# CAA-NMC_variants.net
KiCad netlist of a schematic drawn in EAGLE
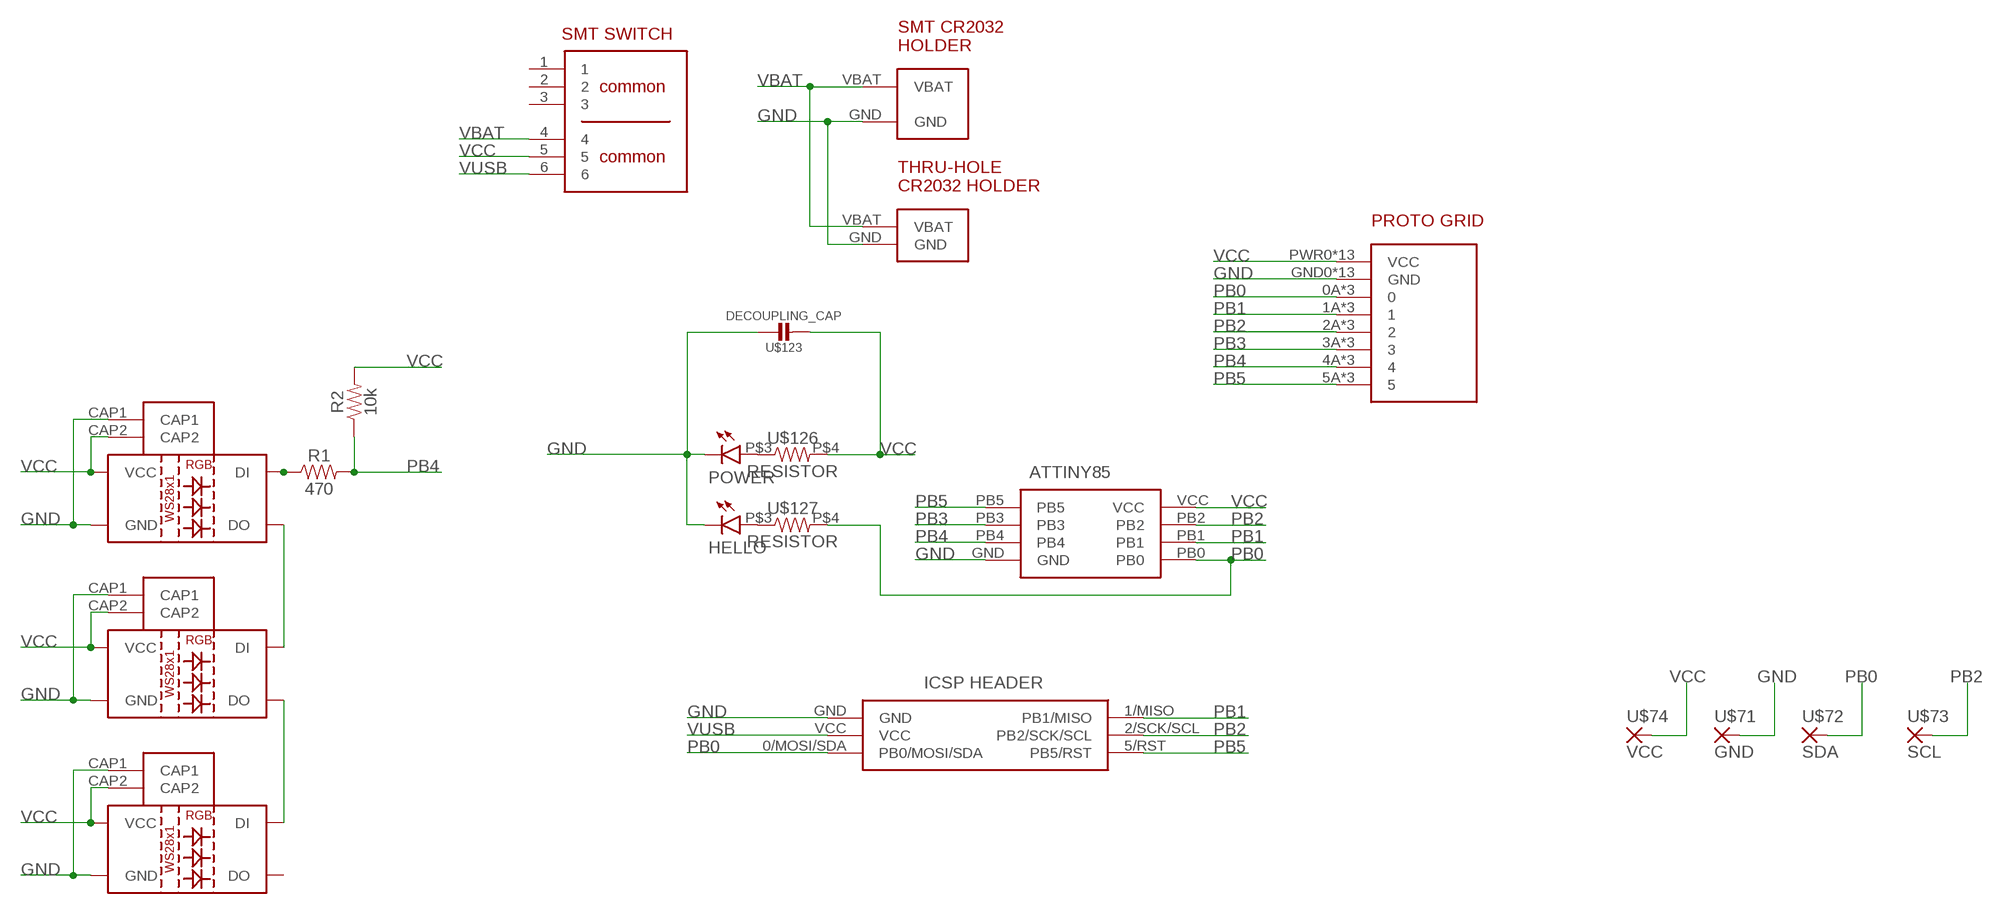
[diagram p0: schematic, sheet 1]

(export (version "E")
  (design (tool "Eeschema 10.0.6"))
  (components
    (comp (ref "D1")
      (value "WS2812B")
      (footprint "eagle-import:WS2812B")
      (libsource (lib "eagle-import") (part "WS2812B"))
    )
    (comp (ref "D2")
      (value "WS2812B")
      (footprint "eagle-import:WS2812B")
      (libsource (lib "eagle-import") (part "WS2812B"))
    )
    (comp (ref "D3")
      (value "WS2812B")
      (footprint "eagle-import:WS2812B")
      (libsource (lib "eagle-import") (part "WS2812B"))
    )
    (comp (ref "HELLO")
      (value "LED3MM")
      (footprint "eagle-import:LED3MM")
      (libsource (lib "eagle-import") (part "LED3MM"))
    )
    (comp (ref "IC1")
      (value "ATTINY85-20SU")
      (footprint "eagle-import:SOT127P798X216-8N")
      (fields (field (name "RS_PART_NUMBER") "1331674"))
      (libsource (lib "eagle-import") (part "ATTINY85-20SU"))
    )
    (comp (ref "J1")
      (value "M20-9980346")
      (footprint "eagle-import:HDRV6W64P254_2X3_762X508X868P")
      (fields (field (name "RS_PART_NUMBER") "7457046P"))
      (libsource (lib "eagle-import") (part "M20-9980346"))
    )
    (comp (ref "POWER")
      (value "LED3MM")
      (footprint "eagle-import:LED3MM")
      (libsource (lib "eagle-import") (part "LED3MM"))
    )
    (comp (ref "R1")
      (value "470")
      (footprint "eagle-import:0603")
      (libsource (lib "eagle-import") (part "470OHM-0603-1/10W-1%"))
    )
    (comp (ref "R2")
      (value "10k")
      (footprint "eagle-import:0603")
      (libsource (lib "eagle-import") (part "10KOHM-0603-1/10W-1%"))
    )
    (comp (ref "U$1")
      (value "PROTO")
      (footprint "eagle-import:PROTO")
      (libsource (lib "eagle-import") (part "PROTO"))
    )
    (comp (ref "U$2")
      (value "SMT-BATTERY-HOLDER")
      (footprint "eagle-import:SMT-CR-HOLDER")
      (libsource (lib "eagle-import") (part "SMT-BATTERY-HOLDER"))
    )
    (comp (ref "U$3")
      (value "THRU-CR-HOLDER")
      (footprint "eagle-import:THRU-CR-HOLDER")
      (libsource (lib "eagle-import") (part "THRU-CR-HOLDER"))
    )
    (comp (ref "U$71")
      (value "GND")
      (footprint "eagle-import:1X01")
      (libsource (lib "eagle-import") (part "ONE_PAD"))
    )
    (comp (ref "U$72")
      (value "SDA")
      (footprint "eagle-import:1X01")
      (libsource (lib "eagle-import") (part "ONE_PAD"))
    )
    (comp (ref "U$73")
      (value "SCL")
      (footprint "eagle-import:1X01")
      (libsource (lib "eagle-import") (part "ONE_PAD"))
    )
    (comp (ref "U$74")
      (value "VCC")
      (footprint "eagle-import:1X01")
      (libsource (lib "eagle-import") (part "ONE_PAD"))
    )
    (comp (ref "U$123")
      (value "DECOUPLING_CAP")
      (footprint "eagle-import:DECOUPLING_CAP")
      (libsource (lib "eagle-import") (part "DECOUPLING_CAP"))
    )
    (comp (ref "U$126")
      (value "RESISTOR")
      (footprint "eagle-import:AXIAL-0.3")
      (libsource (lib "eagle-import") (part "RESISTOR"))
    )
    (comp (ref "U$127")
      (value "RESISTOR")
      (footprint "eagle-import:AXIAL-0.3")
      (libsource (lib "eagle-import") (part "RESISTOR"))
    )
    (comp (ref "U$145")
      (value "SMT-SWITCH")
      (footprint "eagle-import:SMT-SWITCH")
      (libsource (lib "eagle-import") (part "SMT-SWITCH"))
    )
  )
  (nets
    (net (code "1") (name "/GND") (class "Default")
      (node (ref "D1") (pin "CAP1") (pinfunction "CAP1_CAP1") (pintype "bidirectional"))
      (node (ref "D1") (pin "GND") (pinfunction "GND_GND") (pintype "bidirectional"))
      (node (ref "D2") (pin "CAP1") (pinfunction "CAP1_CAP1") (pintype "bidirectional"))
      (node (ref "D2") (pin "GND") (pinfunction "GND_GND") (pintype "bidirectional"))
      (node (ref "D3") (pin "CAP1") (pinfunction "CAP1_CAP1") (pintype "bidirectional"))
      (node (ref "D3") (pin "GND") (pinfunction "GND_GND") (pintype "bidirectional"))
      (node (ref "HELLO") (pin "NEG") (pinfunction "NEG_NEG") (pintype "passive"))
      (node (ref "IC1") (pin "GND") (pinfunction "GND_GND") (pintype "bidirectional"))
      (node (ref "J1") (pin "GND") (pinfunction "GND_GND") (pintype "bidirectional"))
      (node (ref "POWER") (pin "NEG") (pinfunction "NEG_NEG") (pintype "passive"))
      (node (ref "U$1") (pin "GND0") (pinfunction "GND_GND0") (pintype "bidirectional"))
      (node (ref "U$1") (pin "GND1") (pinfunction "GND_GND1") (pintype "bidirectional"))
      (node (ref "U$1") (pin "GND10") (pinfunction "GND_GND10") (pintype "bidirectional"))
      (node (ref "U$1") (pin "GND11") (pinfunction "GND_GND11") (pintype "bidirectional"))
      (node (ref "U$1") (pin "GND12") (pinfunction "GND_GND12") (pintype "bidirectional"))
      (node (ref "U$1") (pin "GND2") (pinfunction "GND_GND2") (pintype "bidirectional"))
      (node (ref "U$1") (pin "GND3") (pinfunction "GND_GND3") (pintype "bidirectional"))
      (node (ref "U$1") (pin "GND4") (pinfunction "GND_GND4") (pintype "bidirectional"))
      (node (ref "U$1") (pin "GND5") (pinfunction "GND_GND5") (pintype "bidirectional"))
      (node (ref "U$1") (pin "GND6") (pinfunction "GND_GND6") (pintype "bidirectional"))
      (node (ref "U$1") (pin "GND7") (pinfunction "GND_GND7") (pintype "bidirectional"))
      (node (ref "U$1") (pin "GND8") (pinfunction "GND_GND8") (pintype "bidirectional"))
      (node (ref "U$1") (pin "GND9") (pinfunction "GND_GND9") (pintype "bidirectional"))
      (node (ref "U$123") (pin "P$1") (pinfunction "1_P$1") (pintype "passive"))
      (node (ref "U$2") (pin "GND") (pinfunction "GND_GND") (pintype "bidirectional"))
      (node (ref "U$3") (pin "GND") (pinfunction "GND_GND") (pintype "bidirectional"))
      (node (ref "U$71") (pin "P$1") (pinfunction "P_P$1") (pintype "passive"))
    )
    (net (code "2") (name "/PB0") (class "Default")
      (node (ref "IC1") (pin "PB0") (pinfunction "PB0_PB0") (pintype "bidirectional"))
      (node (ref "J1") (pin "0/MOSI/SDA") (pinfunction "PB0/MOSI/SDA_0/MOSI/SDA") (pintype "bidirectional"))
      (node (ref "U$1") (pin "0A") (pinfunction "0_0A") (pintype "bidirectional"))
      (node (ref "U$1") (pin "0B") (pinfunction "0_0B") (pintype "bidirectional"))
      (node (ref "U$1") (pin "0C") (pinfunction "0_0C") (pintype "bidirectional"))
      (node (ref "U$127") (pin "P$4") (pinfunction "2_P$4") (pintype "passive"))
      (node (ref "U$72") (pin "P$1") (pinfunction "P_P$1") (pintype "passive"))
    )
    (net (code "3") (name "/PB1") (class "Default")
      (node (ref "IC1") (pin "PB1") (pinfunction "PB1_PB1") (pintype "bidirectional"))
      (node (ref "J1") (pin "1/MISO") (pinfunction "PB1/MISO_1/MISO") (pintype "bidirectional"))
      (node (ref "U$1") (pin "1A") (pinfunction "1_1A") (pintype "bidirectional"))
      (node (ref "U$1") (pin "1B") (pinfunction "1_1B") (pintype "bidirectional"))
      (node (ref "U$1") (pin "1C") (pinfunction "1_1C") (pintype "bidirectional"))
    )
    (net (code "4") (name "/PB2") (class "Default")
      (node (ref "IC1") (pin "PB2") (pinfunction "PB2_PB2") (pintype "bidirectional"))
      (node (ref "J1") (pin "2/SCK/SCL") (pinfunction "PB2/SCK/SCL_2/SCK/SCL") (pintype "bidirectional"))
      (node (ref "U$1") (pin "2A") (pinfunction "2_2A") (pintype "bidirectional"))
      (node (ref "U$1") (pin "2B") (pinfunction "2_2B") (pintype "bidirectional"))
      (node (ref "U$1") (pin "2C") (pinfunction "2_2C") (pintype "bidirectional"))
      (node (ref "U$73") (pin "P$1") (pinfunction "P_P$1") (pintype "passive"))
    )
    (net (code "5") (name "/PB3") (class "Default")
      (node (ref "IC1") (pin "PB3") (pinfunction "PB3_PB3") (pintype "bidirectional"))
      (node (ref "U$1") (pin "3A") (pinfunction "3_3A") (pintype "bidirectional"))
      (node (ref "U$1") (pin "3B") (pinfunction "3_3B") (pintype "bidirectional"))
      (node (ref "U$1") (pin "3C") (pinfunction "3_3C") (pintype "bidirectional"))
    )
    (net (code "6") (name "/PB4") (class "Default")
      (node (ref "IC1") (pin "PB4") (pinfunction "PB4_PB4") (pintype "bidirectional"))
      (node (ref "R1") (pin "2") (pinfunction "2_2") (pintype "passive"))
      (node (ref "R2") (pin "1") (pinfunction "1_1") (pintype "passive"))
      (node (ref "U$1") (pin "4A") (pinfunction "4_4A") (pintype "bidirectional"))
      (node (ref "U$1") (pin "4B") (pinfunction "4_4B") (pintype "bidirectional"))
      (node (ref "U$1") (pin "4C") (pinfunction "4_4C") (pintype "bidirectional"))
    )
    (net (code "7") (name "/PB5") (class "Default")
      (node (ref "IC1") (pin "PB5") (pinfunction "PB5_PB5") (pintype "bidirectional"))
      (node (ref "J1") (pin "5/RST") (pinfunction "PB5/RST_5/RST") (pintype "bidirectional"))
      (node (ref "U$1") (pin "5A") (pinfunction "5_5A") (pintype "bidirectional"))
      (node (ref "U$1") (pin "5B") (pinfunction "5_5B") (pintype "bidirectional"))
      (node (ref "U$1") (pin "5C") (pinfunction "5_5C") (pintype "bidirectional"))
    )
    (net (code "8") (name "/VBAT") (class "Default")
      (node (ref "U$145") (pin "4") (pinfunction "4_4") (pintype "bidirectional"))
      (node (ref "U$2") (pin "VBAT") (pinfunction "VBAT_VBAT") (pintype "bidirectional"))
      (node (ref "U$3") (pin "VBAT") (pinfunction "VBAT_VBAT") (pintype "bidirectional"))
    )
    (net (code "9") (name "/VCC") (class "Default")
      (node (ref "D1") (pin "CAP2") (pinfunction "CAP2_CAP2") (pintype "bidirectional"))
      (node (ref "D1") (pin "VCC") (pinfunction "VCC_VCC") (pintype "bidirectional"))
      (node (ref "D2") (pin "CAP2") (pinfunction "CAP2_CAP2") (pintype "bidirectional"))
      (node (ref "D2") (pin "VCC") (pinfunction "VCC_VCC") (pintype "bidirectional"))
      (node (ref "D3") (pin "CAP2") (pinfunction "CAP2_CAP2") (pintype "bidirectional"))
      (node (ref "D3") (pin "VCC") (pinfunction "VCC_VCC") (pintype "bidirectional"))
      (node (ref "IC1") (pin "VCC") (pinfunction "VCC_VCC") (pintype "bidirectional"))
      (node (ref "R2") (pin "2") (pinfunction "2_2") (pintype "passive"))
      (node (ref "U$1") (pin "PWR0") (pinfunction "VCC_PWR0") (pintype "bidirectional"))
      (node (ref "U$1") (pin "PWR1") (pinfunction "VCC_PWR1") (pintype "bidirectional"))
      (node (ref "U$1") (pin "PWR10") (pinfunction "VCC_PWR10") (pintype "bidirectional"))
      (node (ref "U$1") (pin "PWR11") (pinfunction "VCC_PWR11") (pintype "bidirectional"))
      (node (ref "U$1") (pin "PWR12") (pinfunction "VCC_PWR12") (pintype "bidirectional"))
      (node (ref "U$1") (pin "PWR2") (pinfunction "VCC_PWR2") (pintype "bidirectional"))
      (node (ref "U$1") (pin "PWR3") (pinfunction "VCC_PWR3") (pintype "bidirectional"))
      (node (ref "U$1") (pin "PWR4") (pinfunction "VCC_PWR4") (pintype "bidirectional"))
      (node (ref "U$1") (pin "PWR5") (pinfunction "VCC_PWR5") (pintype "bidirectional"))
      (node (ref "U$1") (pin "PWR6") (pinfunction "VCC_PWR6") (pintype "bidirectional"))
      (node (ref "U$1") (pin "PWR7") (pinfunction "VCC_PWR7") (pintype "bidirectional"))
      (node (ref "U$1") (pin "PWR8") (pinfunction "VCC_PWR8") (pintype "bidirectional"))
      (node (ref "U$1") (pin "PWR9") (pinfunction "VCC_PWR9") (pintype "bidirectional"))
      (node (ref "U$123") (pin "P$2") (pinfunction "2_P$2") (pintype "passive"))
      (node (ref "U$126") (pin "P$4") (pinfunction "2_P$4") (pintype "passive"))
      (node (ref "U$145") (pin "5") (pinfunction "5_5") (pintype "bidirectional"))
      (node (ref "U$74") (pin "P$1") (pinfunction "P_P$1") (pintype "passive"))
    )
    (net (code "10") (name "/VUSB") (class "Default")
      (node (ref "J1") (pin "VCC") (pinfunction "VCC_VCC") (pintype "bidirectional"))
      (node (ref "U$145") (pin "6") (pinfunction "6_6") (pintype "bidirectional"))
    )
    (net (code "11") (name "Net-(D1-PadDI)") (class "Default")
      (node (ref "D1") (pin "DI") (pinfunction "DI_DI") (pintype "bidirectional"))
      (node (ref "R1") (pin "1") (pinfunction "1_1") (pintype "passive"))
    )
    (net (code "12") (name "Net-(D1-PadDO)") (class "Default")
      (node (ref "D1") (pin "DO") (pinfunction "DO_DO") (pintype "bidirectional"))
      (node (ref "D2") (pin "DI") (pinfunction "DI_DI") (pintype "bidirectional"))
    )
    (net (code "13") (name "Net-(D2-PadDO)") (class "Default")
      (node (ref "D2") (pin "DO") (pinfunction "DO_DO") (pintype "bidirectional"))
      (node (ref "D3") (pin "DI") (pinfunction "DI_DI") (pintype "bidirectional"))
    )
    (net (code "14") (name "Net-(U$126-1)") (class "Default")
      (node (ref "POWER") (pin "POS") (pinfunction "POS_POS") (pintype "passive"))
      (node (ref "U$126") (pin "P$3") (pinfunction "1_P$3") (pintype "passive"))
    )
    (net (code "15") (name "Net-(U$127-1)") (class "Default")
      (node (ref "HELLO") (pin "POS") (pinfunction "POS_POS") (pintype "passive"))
      (node (ref "U$127") (pin "P$3") (pinfunction "1_P$3") (pintype "passive"))
    )
    (net (code "16") (name "unconnected-(D3-PadDO)") (class "Default")
      (node (ref "D3") (pin "DO") (pinfunction "DO_DO") (pintype "bidirectional"))
    )
    (net (code "17") (name "unconnected-(U$145-Pad1)") (class "Default")
      (node (ref "U$145") (pin "1") (pinfunction "1_1") (pintype "bidirectional"))
    )
    (net (code "18") (name "unconnected-(U$145-Pad2)") (class "Default")
      (node (ref "U$145") (pin "2") (pinfunction "2_2") (pintype "bidirectional"))
    )
    (net (code "19") (name "unconnected-(U$145-Pad3)") (class "Default")
      (node (ref "U$145") (pin "3") (pinfunction "3_3") (pintype "bidirectional"))
    )
  )
)
